# hv_io_shutdown.net
KiCad netlist of a schematic drawn in Altium Designer
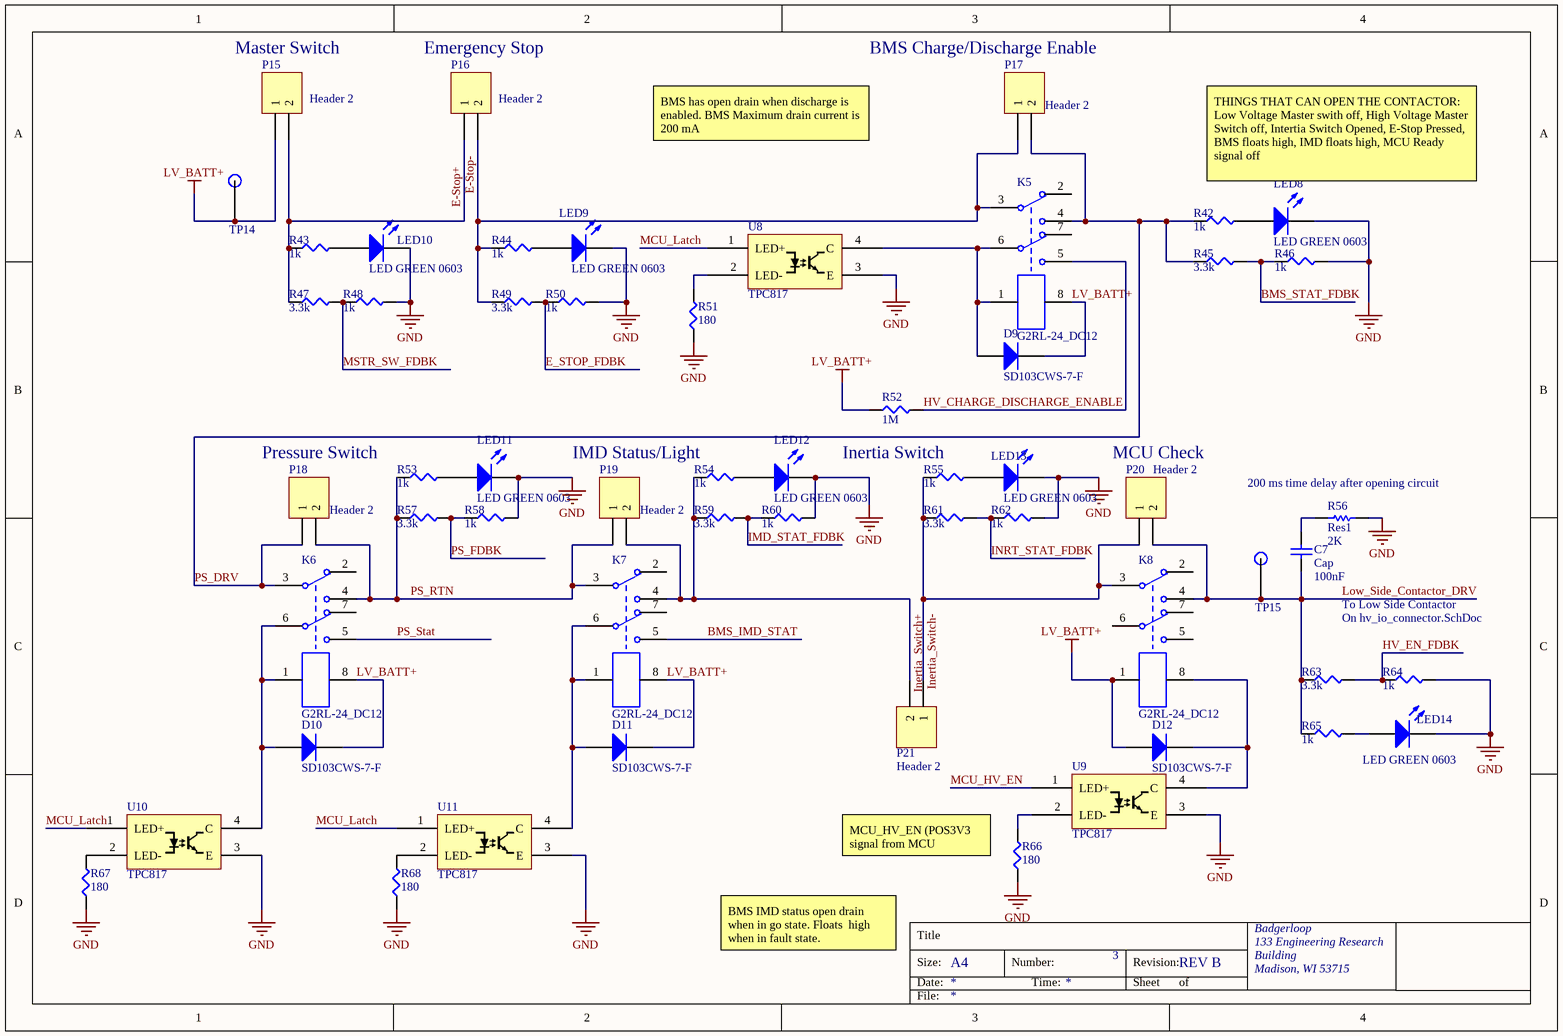
[diagram p0: hv_io_shutdown.SchDoc]

(export (version "E")
  (design (tool "Eeschema 10.0.6"))
  (components
    (comp (ref "C7")
      (value "Cap")
      (footprint "SMD-1206C")
      (description "Capacitor")
      (fields (field (name "ALTIUM_VALUE") "100nF") (field (name "PUBLISHER") "Altium Limited"))
      (libsource (lib "Miscellaneous Devices") (part "Cap"))
    )
    (comp (ref "D9")
      (value "SD103CWS-7-F")
      (footprint "SODFL250X110-2N")
      (description "DIODE GEN PURP 20V 350MA SOD323")
      (fields (field (name "MANUFACTURER") "Diodes Incorporated"))
      (libsource (lib "misc") (part "Diode General Purpose_2"))
    )
    (comp (ref "D10")
      (value "SD103CWS-7-F")
      (footprint "SODFL250X110-2N")
      (description "DIODE GEN PURP 20V 350MA SOD323")
      (fields (field (name "MANUFACTURER") "Diodes Incorporated"))
      (libsource (lib "misc") (part "Diode General Purpose_2"))
    )
    (comp (ref "D11")
      (value "SD103CWS-7-F")
      (footprint "SODFL250X110-2N")
      (description "DIODE GEN PURP 20V 350MA SOD323")
      (fields (field (name "MANUFACTURER") "Diodes Incorporated"))
      (libsource (lib "misc") (part "Diode General Purpose_2"))
    )
    (comp (ref "D12")
      (value "SD103CWS-7-F")
      (footprint "SODFL250X110-2N")
      (description "DIODE GEN PURP 20V 350MA SOD323")
      (fields (field (name "MANUFACTURER") "Diodes Incorporated"))
      (libsource (lib "misc") (part "Diode General Purpose_2"))
    )
    (comp (ref "K5")
      (value "G2RL-24_DC12")
      (footprint "G2RL")
      (description "RELAY GEN PURPOSE DPDT 8A 12V")
      (fields (field (name "MANUFACTURER") "Omron Electronics"))
      (libsource (lib "misc") (part "G2RL-24_DC12"))
    )
    (comp (ref "K6")
      (value "G2RL-24_DC12")
      (footprint "G2RL")
      (description "RELAY GEN PURPOSE DPDT 8A 12V")
      (fields (field (name "MANUFACTURER") "Omron Electronics"))
      (libsource (lib "misc") (part "G2RL-24_DC12"))
    )
    (comp (ref "K7")
      (value "G2RL-24_DC12")
      (footprint "G2RL")
      (description "RELAY GEN PURPOSE DPDT 8A 12V")
      (fields (field (name "MANUFACTURER") "Omron Electronics"))
      (libsource (lib "misc") (part "G2RL-24_DC12"))
    )
    (comp (ref "K8")
      (value "G2RL-24_DC12")
      (footprint "G2RL")
      (description "RELAY GEN PURPOSE DPDT 8A 12V")
      (fields (field (name "MANUFACTURER") "Omron Electronics"))
      (libsource (lib "misc") (part "G2RL-24_DC12"))
    )
    (comp (ref "LED8")
      (value "LED GREEN 0603")
      (footprint "LED 0603 GREEN")
      (fields (field (name "MANUFACTURER") "Lite-On Inc."))
      (libsource (lib "misc") (part "LED GREEN 0603"))
    )
    (comp (ref "LED9")
      (value "LED GREEN 0603")
      (footprint "LED 0603 GREEN")
      (fields (field (name "MANUFACTURER") "Lite-On Inc."))
      (libsource (lib "misc") (part "LED GREEN 0603"))
    )
    (comp (ref "LED10")
      (value "LED GREEN 0603")
      (footprint "LED 0603 GREEN")
      (fields (field (name "MANUFACTURER") "Lite-On Inc."))
      (libsource (lib "misc") (part "LED GREEN 0603"))
    )
    (comp (ref "LED11")
      (value "LED GREEN 0603")
      (footprint "LED 0603 GREEN")
      (fields (field (name "MANUFACTURER") "Lite-On Inc."))
      (libsource (lib "misc") (part "LED GREEN 0603"))
    )
    (comp (ref "LED12")
      (value "LED GREEN 0603")
      (footprint "LED 0603 GREEN")
      (fields (field (name "MANUFACTURER") "Lite-On Inc."))
      (libsource (lib "misc") (part "LED GREEN 0603"))
    )
    (comp (ref "LED13")
      (value "LED GREEN 0603")
      (footprint "LED 0603 GREEN")
      (fields (field (name "MANUFACTURER") "Lite-On Inc."))
      (libsource (lib "misc") (part "LED GREEN 0603"))
    )
    (comp (ref "LED14")
      (value "LED GREEN 0603")
      (footprint "LED 0603 GREEN")
      (fields (field (name "MANUFACTURER") "Lite-On Inc."))
      (libsource (lib "misc") (part "LED GREEN 0603"))
    )
    (comp (ref "P15")
      (value "Header 2")
      (footprint "Pin Header 1x2 TH Pitch 2.54mm")
      (description "Header, 2-Pin")
      (fields (field (name "PUBLISHER") "Altium Limited"))
      (libsource (lib "") (part "Header 2_1"))
    )
    (comp (ref "P16")
      (value "Header 2")
      (footprint "Pin Header 1x2 TH Pitch 2.54mm")
      (description "Header, 2-Pin")
      (fields (field (name "PUBLISHER") "Altium Limited"))
      (libsource (lib "") (part "Header 2_1"))
    )
    (comp (ref "P17")
      (value "Header 2")
      (footprint "Pin Header 1x2 TH Pitch 2.54mm")
      (description "Header, 2-Pin")
      (fields (field (name "PUBLISHER") "Altium Limited"))
      (libsource (lib "") (part "Header 2_1"))
    )
    (comp (ref "P18")
      (value "Header 2")
      (footprint "Pin Header 1x2 TH Pitch 2.54mm")
      (description "Header, 2-Pin")
      (fields (field (name "PUBLISHER") "Altium Limited"))
      (libsource (lib "") (part "Header 2_1"))
    )
    (comp (ref "P19")
      (value "Header 2")
      (footprint "Pin Header 1x2 TH Pitch 2.54mm")
      (description "Header, 2-Pin")
      (fields (field (name "PUBLISHER") "Altium Limited"))
      (libsource (lib "") (part "Header 2_1"))
    )
    (comp (ref "P20")
      (value "Header 2")
      (footprint "Pin Header 1x2 TH Pitch 2.54mm")
      (description "Header, 2-Pin")
      (fields (field (name "PUBLISHER") "Altium Limited"))
      (libsource (lib "") (part "Header 2_1"))
    )
    (comp (ref "P21")
      (value "Header 2")
      (footprint "Pin Header 1x2 TH Pitch 2.54mm")
      (description "Header, 2-Pin")
      (fields (field (name "PUBLISHER") "Altium Limited"))
      (libsource (lib "connector") (part "Header 2"))
    )
    (comp (ref "R42")
      (value "1k")
      (footprint "SMD-0402-RES")
      (description "RES SMD 1K OHM 5% 1/10W 0402")
      (fields (field (name "PART NUMBER") "ERJ-2GEJ102X") (field (name "DIGI-KEY PART NUMBER") "P1.0KJCT-ND"))
      (libsource (lib "altium-import") (part "root_0_ERJ-2GEJ102X_"))
    )
    (comp (ref "R43")
      (value "1k")
      (footprint "SMD-0402-RES")
      (description "RES SMD 1K OHM 5% 1/10W 0402")
      (fields (field (name "PART NUMBER") "ERJ-2GEJ102X") (field (name "DIGI-KEY PART NUMBER") "P1.0KJCT-ND"))
      (libsource (lib "altium-import") (part "root_0_ERJ-2GEJ102X_"))
    )
    (comp (ref "R44")
      (value "1k")
      (footprint "SMD-0402-RES")
      (description "RES SMD 1K OHM 5% 1/10W 0402")
      (fields (field (name "PART NUMBER") "ERJ-2GEJ102X") (field (name "DIGI-KEY PART NUMBER") "P1.0KJCT-ND"))
      (libsource (lib "altium-import") (part "root_0_ERJ-2GEJ102X_"))
    )
    (comp (ref "R45")
      (value "3.3k")
      (footprint "SMD-0402-RES")
      (description "RES SMD 3.3K OHM 5% 1/10W 0402")
      (fields (field (name "PART NUMBER") "ERJ-2GEJ332X") (field (name "DIGI-KEY PART NUMBER") "P3.3KJCT-ND"))
      (libsource (lib "altium-import") (part "root_0_ERJ-2GEJ332X_"))
    )
    (comp (ref "R46")
      (value "1k")
      (footprint "SMD-0402-RES")
      (description "RES SMD 1K OHM 5% 1/10W 0402")
      (fields (field (name "PART NUMBER") "ERJ-2GEJ102X") (field (name "DIGI-KEY PART NUMBER") "P1.0KJCT-ND"))
      (libsource (lib "altium-import") (part "root_0_ERJ-2GEJ102X_"))
    )
    (comp (ref "R47")
      (value "3.3k")
      (footprint "SMD-0402-RES")
      (description "RES SMD 3.3K OHM 5% 1/10W 0402")
      (fields (field (name "PART NUMBER") "ERJ-2GEJ332X") (field (name "DIGI-KEY PART NUMBER") "P3.3KJCT-ND"))
      (libsource (lib "altium-import") (part "root_0_ERJ-2GEJ332X_"))
    )
    (comp (ref "R48")
      (value "1k")
      (footprint "SMD-0402-RES")
      (description "RES SMD 1K OHM 5% 1/10W 0402")
      (fields (field (name "PART NUMBER") "ERJ-2GEJ102X") (field (name "DIGI-KEY PART NUMBER") "P1.0KJCT-ND"))
      (libsource (lib "altium-import") (part "root_0_ERJ-2GEJ102X_"))
    )
    (comp (ref "R49")
      (value "3.3k")
      (footprint "SMD-0402-RES")
      (description "RES SMD 3.3K OHM 5% 1/10W 0402")
      (fields (field (name "PART NUMBER") "ERJ-2GEJ332X") (field (name "DIGI-KEY PART NUMBER") "P3.3KJCT-ND"))
      (libsource (lib "altium-import") (part "root_0_ERJ-2GEJ332X_"))
    )
    (comp (ref "R50")
      (value "1k")
      (footprint "SMD-0402-RES")
      (description "RES SMD 1K OHM 5% 1/10W 0402")
      (fields (field (name "PART NUMBER") "ERJ-2GEJ102X") (field (name "DIGI-KEY PART NUMBER") "P1.0KJCT-ND"))
      (libsource (lib "altium-import") (part "root_0_ERJ-2GEJ102X_"))
    )
    (comp (ref "R51")
      (value "180")
      (footprint "SMD-1206-RES")
      (description "RES SMD 180 OHM 1% 1/4W 1206")
      (fields (field (name "PART NUMBER") "ERJ-8ENF1800V") (field (name "DIGI-KEY PART NUMBER") "P180FCT-ND"))
      (libsource (lib "resistor") (part "ERJ-8ENF1800V"))
    )
    (comp (ref "R52")
      (value "1M")
      (footprint "SMD-0805-RES")
      (description "RES SMD 1M OHM 5% 1/2W 0805")
      (fields
        (field (name "PART NUMBER") "ERJ-P06J105V")
        (field (name "DIGI-KEY PART NUMBER") "P1.0MADCT-ND")
      )
      (libsource (lib "resistor") (part "ERJ-P06J105V"))
    )
    (comp (ref "R53")
      (value "1k")
      (footprint "SMD-0402-RES")
      (description "RES SMD 1K OHM 5% 1/10W 0402")
      (fields (field (name "PART NUMBER") "ERJ-2GEJ102X") (field (name "DIGI-KEY PART NUMBER") "P1.0KJCT-ND"))
      (libsource (lib "altium-import") (part "root_0_ERJ-2GEJ102X_"))
    )
    (comp (ref "R54")
      (value "1k")
      (footprint "SMD-0402-RES")
      (description "RES SMD 1K OHM 5% 1/10W 0402")
      (fields (field (name "PART NUMBER") "ERJ-2GEJ102X") (field (name "DIGI-KEY PART NUMBER") "P1.0KJCT-ND"))
      (libsource (lib "altium-import") (part "root_0_ERJ-2GEJ102X_"))
    )
    (comp (ref "R55")
      (value "1k")
      (footprint "SMD-0402-RES")
      (description "RES SMD 1K OHM 5% 1/10W 0402")
      (fields (field (name "PART NUMBER") "ERJ-2GEJ102X") (field (name "DIGI-KEY PART NUMBER") "P1.0KJCT-ND"))
      (libsource (lib "altium-import") (part "root_0_ERJ-2GEJ102X_"))
    )
    (comp (ref "R56")
      (value "Res1")
      (footprint "SMD-1206-RES")
      (description "Resistor")
      (fields (field (name "ALTIUM_VALUE") "2K") (field (name "PUBLISHER") "Altium Limited"))
      (libsource (lib "Miscellaneous Devices") (part "Res1"))
    )
    (comp (ref "R57")
      (value "3.3k")
      (footprint "SMD-0402-RES")
      (description "RES SMD 3.3K OHM 5% 1/10W 0402")
      (fields (field (name "PART NUMBER") "ERJ-2GEJ332X") (field (name "DIGI-KEY PART NUMBER") "P3.3KJCT-ND"))
      (libsource (lib "altium-import") (part "root_0_ERJ-2GEJ332X_"))
    )
    (comp (ref "R58")
      (value "1k")
      (footprint "SMD-0402-RES")
      (description "RES SMD 1K OHM 5% 1/10W 0402")
      (fields (field (name "PART NUMBER") "ERJ-2GEJ102X") (field (name "DIGI-KEY PART NUMBER") "P1.0KJCT-ND"))
      (libsource (lib "altium-import") (part "root_0_ERJ-2GEJ102X_"))
    )
    (comp (ref "R59")
      (value "3.3k")
      (footprint "SMD-0402-RES")
      (description "RES SMD 3.3K OHM 5% 1/10W 0402")
      (fields (field (name "PART NUMBER") "ERJ-2GEJ332X") (field (name "DIGI-KEY PART NUMBER") "P3.3KJCT-ND"))
      (libsource (lib "altium-import") (part "root_0_ERJ-2GEJ332X_"))
    )
    (comp (ref "R60")
      (value "1k")
      (footprint "SMD-0402-RES")
      (description "RES SMD 1K OHM 5% 1/10W 0402")
      (fields (field (name "PART NUMBER") "ERJ-2GEJ102X") (field (name "DIGI-KEY PART NUMBER") "P1.0KJCT-ND"))
      (libsource (lib "altium-import") (part "root_0_ERJ-2GEJ102X_"))
    )
    (comp (ref "R61")
      (value "3.3k")
      (footprint "SMD-0402-RES")
      (description "RES SMD 3.3K OHM 5% 1/10W 0402")
      (fields (field (name "PART NUMBER") "ERJ-2GEJ332X") (field (name "DIGI-KEY PART NUMBER") "P3.3KJCT-ND"))
      (libsource (lib "altium-import") (part "root_0_ERJ-2GEJ332X_"))
    )
    (comp (ref "R62")
      (value "1k")
      (footprint "SMD-0402-RES")
      (description "RES SMD 1K OHM 5% 1/10W 0402")
      (fields (field (name "PART NUMBER") "ERJ-2GEJ102X") (field (name "DIGI-KEY PART NUMBER") "P1.0KJCT-ND"))
      (libsource (lib "altium-import") (part "root_0_ERJ-2GEJ102X_"))
    )
    (comp (ref "R63")
      (value "3.3k")
      (footprint "SMD-0402-RES")
      (description "RES SMD 3.3K OHM 5% 1/10W 0402")
      (fields (field (name "PART NUMBER") "ERJ-2GEJ332X") (field (name "DIGI-KEY PART NUMBER") "P3.3KJCT-ND"))
      (libsource (lib "altium-import") (part "root_0_ERJ-2GEJ332X_"))
    )
    (comp (ref "R64")
      (value "1k")
      (footprint "SMD-0402-RES")
      (description "RES SMD 1K OHM 5% 1/10W 0402")
      (fields (field (name "PART NUMBER") "ERJ-2GEJ102X") (field (name "DIGI-KEY PART NUMBER") "P1.0KJCT-ND"))
      (libsource (lib "altium-import") (part "root_0_ERJ-2GEJ102X_"))
    )
    (comp (ref "R65")
      (value "1k")
      (footprint "SMD-0402-RES")
      (description "RES SMD 1K OHM 5% 1/10W 0402")
      (fields (field (name "PART NUMBER") "ERJ-2GEJ102X") (field (name "DIGI-KEY PART NUMBER") "P1.0KJCT-ND"))
      (libsource (lib "altium-import") (part "root_0_ERJ-2GEJ102X_"))
    )
    (comp (ref "R66")
      (value "180")
      (footprint "SMD-1206-RES")
      (description "RES SMD 180 OHM 1% 1/4W 1206")
      (fields (field (name "PART NUMBER") "ERJ-8ENF1800V") (field (name "DIGI-KEY PART NUMBER") "P180FCT-ND"))
      (libsource (lib "resistor") (part "ERJ-8ENF1800V"))
    )
    (comp (ref "R67")
      (value "180")
      (footprint "SMD-1206-RES")
      (description "RES SMD 180 OHM 1% 1/4W 1206")
      (fields (field (name "PART NUMBER") "ERJ-8ENF1800V") (field (name "DIGI-KEY PART NUMBER") "P180FCT-ND"))
      (libsource (lib "resistor") (part "ERJ-8ENF1800V"))
    )
    (comp (ref "R68")
      (value "180")
      (footprint "SMD-1206-RES")
      (description "RES SMD 180 OHM 1% 1/4W 1206")
      (fields (field (name "PART NUMBER") "ERJ-8ENF1800V") (field (name "DIGI-KEY PART NUMBER") "P180FCT-ND"))
      (libsource (lib "resistor") (part "ERJ-8ENF1800V"))
    )
    (comp (ref "TP14") (value "TP") (footprint "Test Point") (libsource (lib "misc") (part "TP")))
    (comp (ref "TP15") (value "TP") (footprint "Test Point") (libsource (lib "misc") (part "TP")))
    (comp (ref "U8")
      (value "TPC817")
      (footprint "SOT200P1005X328-5N")
      (description "OPTOISO 5KV TRANS 4SOP")
      (fields (field (name "MANUFACTURER") "Taiwan Semi"))
      (libsource (lib "ic") (part "TPC817"))
    )
    (comp (ref "U9")
      (value "TPC817")
      (footprint "SOT200P1005X328-5N")
      (description "OPTOISO 5KV TRANS 4SOP")
      (fields (field (name "MANUFACTURER") "Taiwan Semi"))
      (libsource (lib "ic") (part "TPC817"))
    )
    (comp (ref "U10")
      (value "TPC817")
      (footprint "SOT200P1005X328-5N")
      (description "OPTOISO 5KV TRANS 4SOP")
      (fields (field (name "MANUFACTURER") "Taiwan Semi"))
      (libsource (lib "ic") (part "TPC817"))
    )
    (comp (ref "U11")
      (value "TPC817")
      (footprint "SOT200P1005X328-5N")
      (description "OPTOISO 5KV TRANS 4SOP")
      (fields (field (name "MANUFACTURER") "Taiwan Semi"))
      (libsource (lib "ic") (part "TPC817"))
    )
  )
  (nets
    (net (code "1") (name "/BMS_IMD_STAT") (class "Default")
      (node (ref "K7") (pin "5") (pinfunction "5_5") (pintype "passive"))
    )
    (net (code "2") (name "/BMS_STAT_FDBK") (class "Default")
      (node (ref "R45") (pin "2") (pinfunction "2_2") (pintype "passive"))
      (node (ref "R46") (pin "1") (pinfunction "1_1") (pintype "passive"))
    )
    (net (code "3") (name "/E-Stop+") (class "Default")
      (node (ref "P15") (pin "2") (pinfunction "2_2") (pintype "passive"))
      (node (ref "P16") (pin "1") (pinfunction "1_1") (pintype "passive"))
      (node (ref "R43") (pin "1") (pinfunction "1_1") (pintype "passive"))
      (node (ref "R47") (pin "1") (pinfunction "1_1") (pintype "passive"))
    )
    (net (code "4") (name "/E-Stop-") (class "Default")
      (node (ref "K5") (pin "3") (pinfunction "3_3") (pintype "passive"))
      (node (ref "P16") (pin "2") (pinfunction "2_2") (pintype "passive"))
      (node (ref "P17") (pin "1") (pinfunction "1_1") (pintype "passive"))
      (node (ref "R44") (pin "1") (pinfunction "1_1") (pintype "passive"))
      (node (ref "R49") (pin "1") (pinfunction "1_1") (pintype "passive"))
    )
    (net (code "5") (name "/E_STOP_FDBK") (class "Default")
      (node (ref "R49") (pin "2") (pinfunction "2_2") (pintype "passive"))
      (node (ref "R50") (pin "1") (pinfunction "1_1") (pintype "passive"))
    )
    (net (code "6") (name "/HV_CHARGE_DISCHARGE_ENABLE") (class "Default")
      (node (ref "K5") (pin "5") (pinfunction "5_5") (pintype "passive"))
      (node (ref "R52") (pin "2") (pinfunction "2_2") (pintype "passive"))
    )
    (net (code "7") (name "/HV_EN_FDBK") (class "Default")
      (node (ref "R63") (pin "2") (pinfunction "2_2") (pintype "passive"))
      (node (ref "R64") (pin "1") (pinfunction "1_1") (pintype "passive"))
    )
    (net (code "8") (name "/IMD_STAT_FDBK") (class "Default")
      (node (ref "R59") (pin "2") (pinfunction "2_2") (pintype "passive"))
      (node (ref "R60") (pin "1") (pinfunction "1_1") (pintype "passive"))
    )
    (net (code "9") (name "/INRT_STAT_FDBK") (class "Default")
      (node (ref "R61") (pin "2") (pinfunction "2_2") (pintype "passive"))
      (node (ref "R62") (pin "1") (pinfunction "1_1") (pintype "passive"))
    )
    (net (code "10") (name "/Inertia_Switch+") (class "Default")
      (node (ref "K7") (pin "4") (pinfunction "4_4") (pintype "passive"))
      (node (ref "P19") (pin "2") (pinfunction "2_2") (pintype "passive"))
      (node (ref "P21") (pin "2") (pinfunction "2_2") (pintype "passive"))
      (node (ref "R54") (pin "1") (pinfunction "1_1") (pintype "passive"))
      (node (ref "R59") (pin "1") (pinfunction "1_1") (pintype "passive"))
    )
    (net (code "11") (name "/Inertia_Switch-") (class "Default")
      (node (ref "K8") (pin "3") (pinfunction "3_3") (pintype "passive"))
      (node (ref "P20") (pin "1") (pinfunction "1_1") (pintype "passive"))
      (node (ref "P21") (pin "1") (pinfunction "1_1") (pintype "passive"))
      (node (ref "R55") (pin "1") (pinfunction "1_1") (pintype "passive"))
      (node (ref "R61") (pin "1") (pinfunction "1_1") (pintype "passive"))
    )
    (net (code "12") (name "/Low_Side_Contactor_DRV") (class "Default")
      (node (ref "C7") (pin "1") (pinfunction "1_1") (pintype "passive"))
      (node (ref "K8") (pin "4") (pinfunction "4_4") (pintype "passive"))
      (node (ref "P20") (pin "2") (pinfunction "2_2") (pintype "passive"))
      (node (ref "R63") (pin "1") (pinfunction "1_1") (pintype "passive"))
      (node (ref "R65") (pin "1") (pinfunction "1_1") (pintype "passive"))
      (node (ref "TP15") (pin "1") (pinfunction "1_1") (pintype "passive"))
    )
    (net (code "13") (name "/MCU_HV_EN") (class "Default")
      (node (ref "U9") (pin "1") (pinfunction "LED+_1") (pintype "passive"))
    )
    (net (code "14") (name "/MCU_Latch") (class "Default")
      (node (ref "U10") (pin "1") (pinfunction "LED+_1") (pintype "passive"))
      (node (ref "U11") (pin "1") (pinfunction "LED+_1") (pintype "passive"))
      (node (ref "U8") (pin "1") (pinfunction "LED+_1") (pintype "passive"))
    )
    (net (code "15") (name "/MSTR_SW_FDBK") (class "Default")
      (node (ref "R47") (pin "2") (pinfunction "2_2") (pintype "passive"))
      (node (ref "R48") (pin "1") (pinfunction "1_1") (pintype "passive"))
    )
    (net (code "16") (name "/PS_DRV") (class "Default")
      (node (ref "K5") (pin "4") (pinfunction "4_4") (pintype "passive"))
      (node (ref "K6") (pin "3") (pinfunction "3_3") (pintype "passive"))
      (node (ref "P17") (pin "2") (pinfunction "2_2") (pintype "passive"))
      (node (ref "P18") (pin "1") (pinfunction "1_1") (pintype "passive"))
      (node (ref "R42") (pin "1") (pinfunction "1_1") (pintype "passive"))
      (node (ref "R45") (pin "1") (pinfunction "1_1") (pintype "passive"))
    )
    (net (code "17") (name "/PS_FDBK") (class "Default")
      (node (ref "R57") (pin "2") (pinfunction "2_2") (pintype "passive"))
      (node (ref "R58") (pin "1") (pinfunction "1_1") (pintype "passive"))
    )
    (net (code "18") (name "/PS_RTN") (class "Default")
      (node (ref "K6") (pin "4") (pinfunction "4_4") (pintype "passive"))
      (node (ref "K7") (pin "3") (pinfunction "3_3") (pintype "passive"))
      (node (ref "P18") (pin "2") (pinfunction "2_2") (pintype "passive"))
      (node (ref "P19") (pin "1") (pinfunction "1_1") (pintype "passive"))
      (node (ref "R53") (pin "1") (pinfunction "1_1") (pintype "passive"))
      (node (ref "R57") (pin "1") (pinfunction "1_1") (pintype "passive"))
    )
    (net (code "19") (name "/PS_Stat") (class "Default")
      (node (ref "K6") (pin "5") (pinfunction "5_5") (pintype "passive"))
    )
    (net (code "20") (name "GND") (class "Default")
      (node (ref "LED10") (pin "2") (pinfunction "K_2") (pintype "passive"))
      (node (ref "LED11") (pin "2") (pinfunction "K_2") (pintype "passive"))
      (node (ref "LED12") (pin "2") (pinfunction "K_2") (pintype "passive"))
      (node (ref "LED13") (pin "2") (pinfunction "K_2") (pintype "passive"))
      (node (ref "LED14") (pin "2") (pinfunction "K_2") (pintype "passive"))
      (node (ref "LED8") (pin "2") (pinfunction "K_2") (pintype "passive"))
      (node (ref "LED9") (pin "2") (pinfunction "K_2") (pintype "passive"))
      (node (ref "R46") (pin "2") (pinfunction "2_2") (pintype "passive"))
      (node (ref "R48") (pin "2") (pinfunction "2_2") (pintype "passive"))
      (node (ref "R50") (pin "2") (pinfunction "2_2") (pintype "passive"))
      (node (ref "R51") (pin "1") (pinfunction "1_1") (pintype "passive"))
      (node (ref "R56") (pin "2") (pinfunction "2_2") (pintype "passive"))
      (node (ref "R58") (pin "2") (pinfunction "2_2") (pintype "passive"))
      (node (ref "R60") (pin "2") (pinfunction "2_2") (pintype "passive"))
      (node (ref "R62") (pin "2") (pinfunction "2_2") (pintype "passive"))
      (node (ref "R64") (pin "2") (pinfunction "2_2") (pintype "passive"))
      (node (ref "R66") (pin "1") (pinfunction "1_1") (pintype "passive"))
      (node (ref "R67") (pin "1") (pinfunction "1_1") (pintype "passive"))
      (node (ref "R68") (pin "1") (pinfunction "1_1") (pintype "passive"))
      (node (ref "U10") (pin "3") (pinfunction "E_3") (pintype "passive"))
      (node (ref "U11") (pin "3") (pinfunction "E_3") (pintype "passive"))
      (node (ref "U8") (pin "3") (pinfunction "E_3") (pintype "passive"))
      (node (ref "U9") (pin "3") (pinfunction "E_3") (pintype "passive"))
    )
    (net (code "21") (name "LV_BATT+") (class "Default")
      (node (ref "D10") (pin "2") (pinfunction "K_2") (pintype "passive"))
      (node (ref "D11") (pin "2") (pinfunction "K_2") (pintype "passive"))
      (node (ref "D12") (pin "1") (pinfunction "A_1") (pintype "passive"))
      (node (ref "D9") (pin "2") (pinfunction "K_2") (pintype "passive"))
      (node (ref "K5") (pin "8") (pinfunction "8_8") (pintype "passive"))
      (node (ref "K6") (pin "8") (pinfunction "8_8") (pintype "passive"))
      (node (ref "K7") (pin "8") (pinfunction "8_8") (pintype "passive"))
      (node (ref "K8") (pin "1") (pinfunction "1_1") (pintype "passive"))
      (node (ref "P15") (pin "1") (pinfunction "1_1") (pintype "passive"))
      (node (ref "R52") (pin "1") (pinfunction "1_1") (pintype "passive"))
      (node (ref "TP14") (pin "1") (pinfunction "1_1") (pintype "passive"))
    )
    (net (code "22") (name "Net-(C7-Pad2)") (class "Default")
      (node (ref "C7") (pin "2") (pinfunction "2_2") (pintype "passive"))
      (node (ref "R56") (pin "1") (pinfunction "1_1") (pintype "passive"))
    )
    (net (code "23") (name "Net-(D9-A)") (class "Default")
      (node (ref "D9") (pin "1") (pinfunction "A_1") (pintype "passive"))
      (node (ref "K5") (pin "1") (pinfunction "1_1") (pintype "passive"))
      (node (ref "K5") (pin "6") (pinfunction "6_6") (pintype "passive"))
      (node (ref "U8") (pin "4") (pinfunction "C_4") (pintype "passive"))
    )
    (net (code "24") (name "Net-(D10-A)") (class "Default")
      (node (ref "D10") (pin "1") (pinfunction "A_1") (pintype "passive"))
      (node (ref "K6") (pin "1") (pinfunction "1_1") (pintype "passive"))
      (node (ref "K6") (pin "6") (pinfunction "6_6") (pintype "passive"))
      (node (ref "U10") (pin "4") (pinfunction "C_4") (pintype "passive"))
    )
    (net (code "25") (name "Net-(D11-A)") (class "Default")
      (node (ref "D11") (pin "1") (pinfunction "A_1") (pintype "passive"))
      (node (ref "K7") (pin "1") (pinfunction "1_1") (pintype "passive"))
      (node (ref "K7") (pin "6") (pinfunction "6_6") (pintype "passive"))
      (node (ref "U11") (pin "4") (pinfunction "C_4") (pintype "passive"))
    )
    (net (code "26") (name "Net-(D12-K)") (class "Default")
      (node (ref "D12") (pin "2") (pinfunction "K_2") (pintype "passive"))
      (node (ref "K8") (pin "8") (pinfunction "8_8") (pintype "passive"))
      (node (ref "U9") (pin "4") (pinfunction "C_4") (pintype "passive"))
    )
    (net (code "27") (name "Net-(LED8-A)") (class "Default")
      (node (ref "LED8") (pin "1") (pinfunction "A_1") (pintype "passive"))
      (node (ref "R42") (pin "2") (pinfunction "2_2") (pintype "passive"))
    )
    (net (code "28") (name "Net-(LED9-A)") (class "Default")
      (node (ref "LED9") (pin "1") (pinfunction "A_1") (pintype "passive"))
      (node (ref "R44") (pin "2") (pinfunction "2_2") (pintype "passive"))
    )
    (net (code "29") (name "Net-(LED10-A)") (class "Default")
      (node (ref "LED10") (pin "1") (pinfunction "A_1") (pintype "passive"))
      (node (ref "R43") (pin "2") (pinfunction "2_2") (pintype "passive"))
    )
    (net (code "30") (name "Net-(LED11-A)") (class "Default")
      (node (ref "LED11") (pin "1") (pinfunction "A_1") (pintype "passive"))
      (node (ref "R53") (pin "2") (pinfunction "2_2") (pintype "passive"))
    )
    (net (code "31") (name "Net-(LED12-A)") (class "Default")
      (node (ref "LED12") (pin "1") (pinfunction "A_1") (pintype "passive"))
      (node (ref "R54") (pin "2") (pinfunction "2_2") (pintype "passive"))
    )
    (net (code "32") (name "Net-(LED13-A)") (class "Default")
      (node (ref "LED13") (pin "1") (pinfunction "A_1") (pintype "passive"))
      (node (ref "R55") (pin "2") (pinfunction "2_2") (pintype "passive"))
    )
    (net (code "33") (name "Net-(LED14-A)") (class "Default")
      (node (ref "LED14") (pin "1") (pinfunction "A_1") (pintype "passive"))
      (node (ref "R65") (pin "2") (pinfunction "2_2") (pintype "passive"))
    )
    (net (code "34") (name "Net-(U8-LED-)") (class "Default")
      (node (ref "R51") (pin "2") (pinfunction "2_2") (pintype "passive"))
      (node (ref "U8") (pin "2") (pinfunction "LED-_2") (pintype "passive"))
    )
    (net (code "35") (name "Net-(U9-LED-)") (class "Default")
      (node (ref "R66") (pin "2") (pinfunction "2_2") (pintype "passive"))
      (node (ref "U9") (pin "2") (pinfunction "LED-_2") (pintype "passive"))
    )
    (net (code "36") (name "Net-(U10-LED-)") (class "Default")
      (node (ref "R67") (pin "2") (pinfunction "2_2") (pintype "passive"))
      (node (ref "U10") (pin "2") (pinfunction "LED-_2") (pintype "passive"))
    )
    (net (code "37") (name "Net-(U11-LED-)") (class "Default")
      (node (ref "R68") (pin "2") (pinfunction "2_2") (pintype "passive"))
      (node (ref "U11") (pin "2") (pinfunction "LED-_2") (pintype "passive"))
    )
    (net (code "38") (name "unconnected-(K5-Pad2)") (class "Default")
      (node (ref "K5") (pin "2") (pinfunction "2_2") (pintype "passive"))
    )
    (net (code "39") (name "unconnected-(K5-Pad7)") (class "Default")
      (node (ref "K5") (pin "7") (pinfunction "7_7") (pintype "passive"))
    )
    (net (code "40") (name "unconnected-(K6-Pad2)") (class "Default")
      (node (ref "K6") (pin "2") (pinfunction "2_2") (pintype "passive"))
    )
    (net (code "41") (name "unconnected-(K6-Pad7)") (class "Default")
      (node (ref "K6") (pin "7") (pinfunction "7_7") (pintype "passive"))
    )
    (net (code "42") (name "unconnected-(K7-Pad2)") (class "Default")
      (node (ref "K7") (pin "2") (pinfunction "2_2") (pintype "passive"))
    )
    (net (code "43") (name "unconnected-(K7-Pad7)") (class "Default")
      (node (ref "K7") (pin "7") (pinfunction "7_7") (pintype "passive"))
    )
    (net (code "44") (name "unconnected-(K8-Pad2)") (class "Default")
      (node (ref "K8") (pin "2") (pinfunction "2_2") (pintype "passive"))
    )
    (net (code "45") (name "unconnected-(K8-Pad5)") (class "Default")
      (node (ref "K8") (pin "5") (pinfunction "5_5") (pintype "passive"))
    )
    (net (code "46") (name "unconnected-(K8-Pad6)") (class "Default")
      (node (ref "K8") (pin "6") (pinfunction "6_6") (pintype "passive"))
    )
    (net (code "47") (name "unconnected-(K8-Pad7)") (class "Default")
      (node (ref "K8") (pin "7") (pinfunction "7_7") (pintype "passive"))
    )
  )
)
